# delyiannis_filter.net
KiCad netlist of a schematic drawn in Altium Designer
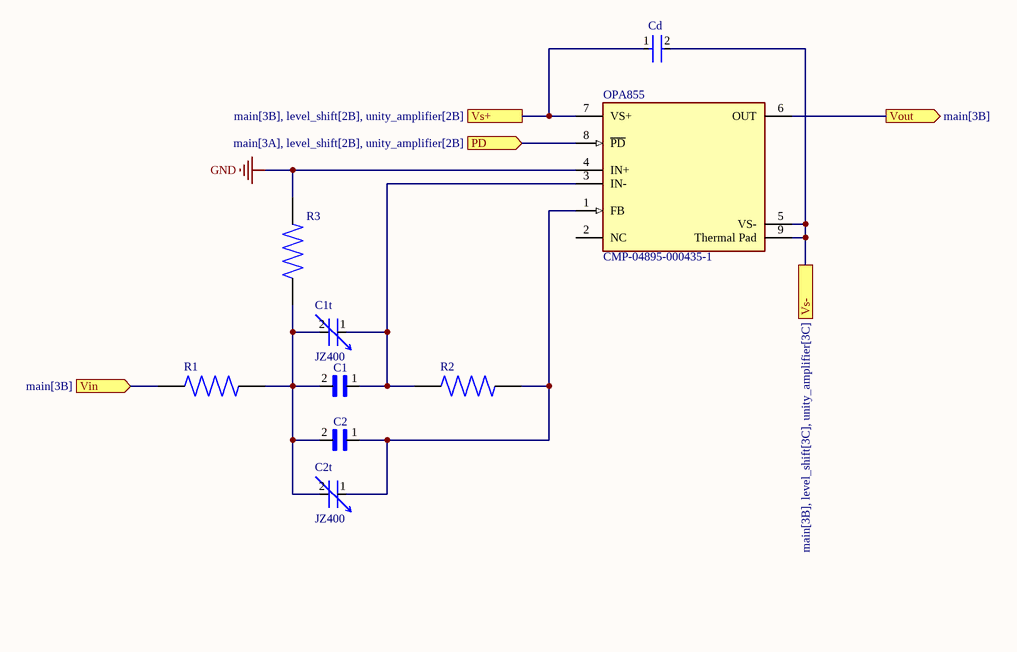
[diagram p0: delyiannis_filter.SchDoc]

(export (version "E")
  (design (tool "Eeschema 10.0.6"))
  (components
    (comp (ref "C1")
      (value "CC0402BRNPO9BN8R2")
      (footprint "CAPC1005X55N")
      (description "KC 8,2pF 0402 0,10pF 50V NP0")
      (libsource (lib "CC0402BRNPO9BN8R2") (part "CC0402BRNPO9BN8R2"))
    )
    (comp (ref "C1t")
      (value "JZ400")
      (footprint "FP-JZ400-MFG")
      (description "CAP TRIMMER 8-40PF 125V SMD")
      (fields (field (name "TOLERANCE") "100%"))
      (libsource (lib "Altium Content Vault") (part "c3dafefa460fab6ae81608f7c2dc7bd"))
    )
    (comp (ref "C2")
      (value "CC0402BRNPO9BN8R2")
      (footprint "CAPC1005X55N")
      (description "KC 8,2pF 0402 0,10pF 50V NP0")
      (libsource (lib "CC0402BRNPO9BN8R2") (part "CC0402BRNPO9BN8R2"))
    )
    (comp (ref "C2t")
      (value "JZ400")
      (footprint "FP-JZ400-MFG")
      (description "CAP TRIMMER 8-40PF 125V SMD")
      (fields (field (name "TOLERANCE") "100%"))
      (libsource (lib "Altium Content Vault") (part "c3dafefa460fab6ae81608f7c2dc7bd"))
    )
    (comp (ref "Cd")
      (value "C0402C104K4RACTU")
      (footprint "FP-C0402-BB-MFG")
      (description "CAP CER 0.1UF 16V X7R 0402")
      (fields
        (field (name "TOLERANCE") "0.1")
        (field (name "OCTOPART") "https://octopart.com/c0402c104k4ractu-kemet-94158")
      )
      (libsource (lib "Altium Content Vault") (part "b4654b650e69147ec39a6b967a45e02"))
    )
    (comp (ref "OPA855")
      (value "CMP-04895-000435-1")
      (footprint "FP-DSG0008A-MFG")
      (description "IC OPAMP GP 1 CIRCUIT 8WSON")
      (libsource (lib "kevin kim") (part "CMP-04895-000435-1"))
    )
    (comp (ref "R1")
      (value "RN73H1ETTP26R4F50")
      (footprint "RESC1005X40N")
      (libsource (lib "RN73H1ETTP26R4F50") (part "RN73H1ETTP26R4F50"))
    )
    (comp (ref "R2")
      (value "RC0603FR-0753R6L")
      (footprint "RESC1608X55N")
      (description "Res Thick Film 0603 53.6 Ohm 1% 0.1W(1/10W) ?100ppm/?C Molded SMD Paper T/R")
      (libsource (lib "RC0603FR-0753R6L") (part "RC0603FR-0753R6L"))
    )
    (comp (ref "R3")
      (value "RMCF0603FT634R")
      (footprint "RESC1508X55N")
      (libsource (lib "RMCF0603FT634R") (part "RMCF0603FT634R"))
    )
  )
  (nets
    (net (code "1") (name "/PD") (class "Default")
      (node (ref "OPA855") (pin "8") (pinfunction "~{PD}_8") (pintype "input"))
    )
    (net (code "2") (name "/Vin") (class "Default")
      (node (ref "R1") (pin "1") (pinfunction "1_1") (pintype "passive"))
    )
    (net (code "3") (name "/Vout") (class "Default")
      (node (ref "OPA855") (pin "6") (pinfunction "OUT_6") (pintype "passive"))
    )
    (net (code "4") (name "/Vs+") (class "Default")
      (node (ref "Cd") (pin "1") (pinfunction "1_1") (pintype "passive"))
      (node (ref "OPA855") (pin "7") (pinfunction "VS+_7") (pintype "power_in"))
    )
    (net (code "5") (name "/Vs-") (class "Default")
      (node (ref "Cd") (pin "2") (pinfunction "2_2") (pintype "passive"))
      (node (ref "OPA855") (pin "5") (pinfunction "VS-_5") (pintype "power_in"))
      (node (ref "OPA855") (pin "9") (pinfunction "Thermal_Pad_9") (pintype "passive"))
    )
    (net (code "6") (name "GND") (class "Default")
      (node (ref "OPA855") (pin "4") (pinfunction "IN+_4") (pintype "tri_state"))
      (node (ref "R3") (pin "1") (pinfunction "1_1") (pintype "passive"))
    )
    (net (code "7") (name "Net-(C1t-COLD)") (class "Default")
      (node (ref "C1") (pin "2") (pinfunction "2_2") (pintype "passive"))
      (node (ref "C1t") (pin "2") (pinfunction "COLD_2") (pintype "passive"))
      (node (ref "C2") (pin "2") (pinfunction "2_2") (pintype "passive"))
      (node (ref "C2t") (pin "2") (pinfunction "COLD_2") (pintype "passive"))
      (node (ref "R1") (pin "2") (pinfunction "2_2") (pintype "passive"))
      (node (ref "R3") (pin "2") (pinfunction "2_2") (pintype "passive"))
    )
    (net (code "8") (name "Net-(C1t-HOT)") (class "Default")
      (node (ref "C1") (pin "1") (pinfunction "1_1") (pintype "passive"))
      (node (ref "C1t") (pin "1") (pinfunction "HOT_1") (pintype "passive"))
      (node (ref "OPA855") (pin "3") (pinfunction "IN-_3") (pintype "tri_state"))
      (node (ref "R2") (pin "1") (pinfunction "1_1") (pintype "passive"))
    )
    (net (code "9") (name "Net-(C2t-HOT)") (class "Default")
      (node (ref "C2") (pin "1") (pinfunction "1_1") (pintype "passive"))
      (node (ref "C2t") (pin "1") (pinfunction "HOT_1") (pintype "passive"))
      (node (ref "OPA855") (pin "1") (pinfunction "FB_1") (pintype "input"))
      (node (ref "R2") (pin "2") (pinfunction "2_2") (pintype "passive"))
    )
    (net (code "10") (name "unconnected-(OPA855-NC-Pad2)") (class "Default")
      (node (ref "OPA855") (pin "2") (pinfunction "NC_2") (pintype "passive"))
    )
  )
)
